# ChladniEagle2.net
KiCad netlist of a schematic drawn in EAGLE
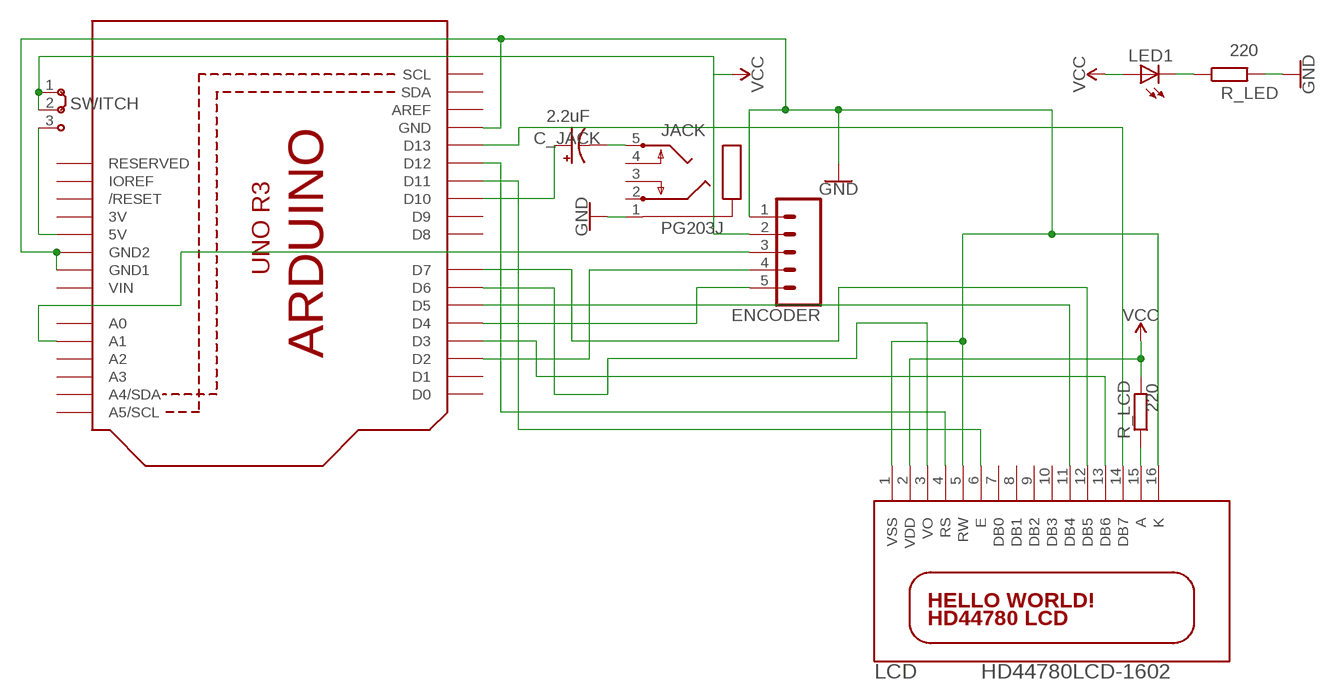
[diagram p0: schematic, sheet 1]

(export (version "E")
  (design (tool "Eeschema 10.0.6"))
  (components
    (comp (ref "C_JACK")
      (value "CPOL-USE2,5-6E")
      (footprint "eagle-import:E2,5-6E")
      (fields (field (name "CAPACITANCIA") "2.2uF"))
      (libsource (lib "eagle-import") (part "CPOL-USE2,5-6E"))
    )
    (comp (ref "ENCODER")
      (value "CONN_05NO_SILK")
      (footprint "eagle-import:1X05_NO_SILK")
      (libsource (lib "eagle-import") (part "CONN_05NO_SILK"))
    )
    (comp (ref "JACK")
      (value "PG203J")
      (footprint "eagle-import:PG203J")
      (libsource (lib "eagle-import") (part "PG203J"))
    )
    (comp (ref "LCD")
      (value "HD44780LCD-1602")
      (footprint "eagle-import:LCD1602")
      (libsource (lib "eagle-import") (part "HD44780LCD-1602"))
    )
    (comp (ref "LED1")
      (value "LED5MM")
      (footprint "eagle-import:LED5MM")
      (libsource (lib "eagle-import") (part "LED5MM"))
    )
    (comp (ref "R_LCD")
      (value "R-EU_0204/7")
      (footprint "eagle-import:0204_7")
      (fields (field (name "RESISTENCIA") "220"))
      (libsource (lib "eagle-import") (part "R-EU_0204/7"))
    )
    (comp (ref "R_LED")
      (value "R-EU_0204/7")
      (footprint "eagle-import:0204_7")
      (fields (field (name "RESISTENCIA") "220"))
      (libsource (lib "eagle-import") (part "R-EU_0204/7"))
    )
    (comp (ref "SWITCH")
      (value "J2X2MM")
      (footprint "eagle-import:04C")
      (libsource (lib "eagle-import") (part "J2X2MM"))
    )
    (comp (ref "U1")
      (value "ARDUINOR3-BPLACE")
      (footprint "eagle-import:ARDUINOR3-BPLACE")
      (libsource (lib "eagle-import") (part "ARDUINOR3-BPLACE"))
    )
  )
  (nets
    (net (code "1") (name "/3V") (class "Default")
      (node (ref "U1") (pin "3V") (pinfunction "3V_3V") (pintype "power_in"))
    )
    (net (code "2") (name "/VIN") (class "Default")
      (node (ref "U1") (pin "VIN") (pinfunction "VIN_VIN") (pintype "power_in"))
    )
    (net (code "3") (name "GND") (class "Default")
      (node (ref "ENCODER") (pin "1") (pinfunction "1_1") (pintype "passive"))
      (node (ref "JACK") (pin "1") (pinfunction "1_1") (pintype "passive"))
      (node (ref "LCD") (pin "1") (pinfunction "VSS_1") (pintype "power_in"))
      (node (ref "LCD") (pin "16") (pinfunction "K_16") (pintype "input"))
      (node (ref "LCD") (pin "5") (pinfunction "RW_5") (pintype "input"))
      (node (ref "R_LED") (pin "2") (pinfunction "2_2") (pintype "passive"))
      (node (ref "U1") (pin "GND") (pinfunction "GND_GND") (pintype "power_in"))
      (node (ref "U1") (pin "GND1") (pinfunction "GND1_GND1") (pintype "power_in"))
      (node (ref "U1") (pin "GND2") (pinfunction "GND2_GND2") (pintype "power_in"))
    )
    (net (code "4") (name "Net-(C_JACK-Pad+)") (class "Default")
      (node (ref "C_JACK") (pin "+") (pinfunction "+_+") (pintype "passive"))
      (node (ref "U1") (pin "D10") (pinfunction "D10_D10") (pintype "bidirectional"))
    )
    (net (code "5") (name "Net-(C_JACK-Pad-)") (class "Default")
      (node (ref "C_JACK") (pin "-") (pinfunction "-_-") (pintype "passive"))
      (node (ref "JACK") (pin "5") (pinfunction "5_5") (pintype "passive"))
    )
    (net (code "6") (name "Net-(ENCODER-Pad3)") (class "Default")
      (node (ref "ENCODER") (pin "3") (pinfunction "3_3") (pintype "passive"))
      (node (ref "U1") (pin "A1") (pinfunction "A1_A1") (pintype "bidirectional"))
    )
    (net (code "7") (name "Net-(ENCODER-Pad4)") (class "Default")
      (node (ref "ENCODER") (pin "4") (pinfunction "4_4") (pintype "passive"))
      (node (ref "U1") (pin "D2") (pinfunction "D2_D2") (pintype "bidirectional"))
    )
    (net (code "8") (name "Net-(ENCODER-Pad5)") (class "Default")
      (node (ref "ENCODER") (pin "5") (pinfunction "5_5") (pintype "passive"))
      (node (ref "U1") (pin "D4") (pinfunction "D4_D4") (pintype "bidirectional"))
    )
    (net (code "9") (name "Net-(LCD-A)") (class "Default")
      (node (ref "LCD") (pin "15") (pinfunction "A_15") (pintype "input"))
      (node (ref "R_LCD") (pin "1") (pinfunction "1_1") (pintype "passive"))
    )
    (net (code "10") (name "Net-(LCD-DB4)") (class "Default")
      (node (ref "LCD") (pin "11") (pinfunction "DB4_11") (pintype "bidirectional"))
      (node (ref "U1") (pin "D5") (pinfunction "D5_D5") (pintype "bidirectional"))
    )
    (net (code "11") (name "Net-(LCD-DB5)") (class "Default")
      (node (ref "LCD") (pin "12") (pinfunction "DB5_12") (pintype "bidirectional"))
      (node (ref "U1") (pin "D7") (pinfunction "D7_D7") (pintype "bidirectional"))
    )
    (net (code "12") (name "Net-(LCD-DB6)") (class "Default")
      (node (ref "LCD") (pin "13") (pinfunction "DB6_13") (pintype "bidirectional"))
      (node (ref "U1") (pin "D3") (pinfunction "D3_D3") (pintype "bidirectional"))
    )
    (net (code "13") (name "Net-(LCD-DB7)") (class "Default")
      (node (ref "LCD") (pin "14") (pinfunction "DB7_14") (pintype "bidirectional"))
      (node (ref "U1") (pin "D13") (pinfunction "D13_D13") (pintype "bidirectional"))
    )
    (net (code "14") (name "Net-(LCD-E)") (class "Default")
      (node (ref "LCD") (pin "6") (pinfunction "E_6") (pintype "input"))
      (node (ref "U1") (pin "D11") (pinfunction "D11_D11") (pintype "bidirectional"))
    )
    (net (code "15") (name "Net-(LCD-RS)") (class "Default")
      (node (ref "LCD") (pin "4") (pinfunction "RS_4") (pintype "input"))
      (node (ref "U1") (pin "D12") (pinfunction "D12_D12") (pintype "bidirectional"))
    )
    (net (code "16") (name "Net-(LCD-VO)") (class "Default")
      (node (ref "LCD") (pin "3") (pinfunction "VO_3") (pintype "input"))
      (node (ref "U1") (pin "D6") (pinfunction "D6_D6") (pintype "bidirectional"))
    )
    (net (code "17") (name "Net-(LED1-C)") (class "Default")
      (node (ref "LED1") (pin "K") (pinfunction "C_K") (pintype "passive"))
      (node (ref "R_LED") (pin "1") (pinfunction "1_1") (pintype "passive"))
    )
    (net (code "18") (name "Net-(SWITCH-Pad3)") (class "Default")
      (node (ref "SWITCH") (pin "3") (pinfunction "3_3") (pintype "passive"))
      (node (ref "U1") (pin "5V") (pinfunction "5V_5V") (pintype "power_in"))
    )
    (net (code "19") (name "VCC") (class "Default")
      (node (ref "ENCODER") (pin "2") (pinfunction "2_2") (pintype "passive"))
      (node (ref "LCD") (pin "2") (pinfunction "VDD_2") (pintype "power_in"))
      (node (ref "LED1") (pin "A") (pinfunction "A_A") (pintype "passive"))
      (node (ref "R_LCD") (pin "2") (pinfunction "2_2") (pintype "passive"))
      (node (ref "SWITCH") (pin "1") (pinfunction "1_1") (pintype "passive"))
      (node (ref "SWITCH") (pin "2") (pinfunction "2_2") (pintype "passive"))
    )
    (net (code "20") (name "unconnected-(JACK-Pad2)") (class "Default")
      (node (ref "JACK") (pin "2") (pinfunction "2_2") (pintype "passive"))
    )
    (net (code "21") (name "unconnected-(JACK-Pad3)") (class "Default")
      (node (ref "JACK") (pin "3") (pinfunction "3_3") (pintype "passive"))
    )
    (net (code "22") (name "unconnected-(JACK-Pad4)") (class "Default")
      (node (ref "JACK") (pin "4") (pinfunction "4_4") (pintype "passive"))
    )
    (net (code "23") (name "unconnected-(LCD-DB0-Pad7)") (class "Default")
      (node (ref "LCD") (pin "7") (pinfunction "DB0_7") (pintype "bidirectional"))
    )
    (net (code "24") (name "unconnected-(LCD-DB1-Pad8)") (class "Default")
      (node (ref "LCD") (pin "8") (pinfunction "DB1_8") (pintype "bidirectional"))
    )
    (net (code "25") (name "unconnected-(LCD-DB2-Pad9)") (class "Default")
      (node (ref "LCD") (pin "9") (pinfunction "DB2_9") (pintype "bidirectional"))
    )
    (net (code "26") (name "unconnected-(LCD-DB3-Pad10)") (class "Default")
      (node (ref "LCD") (pin "10") (pinfunction "DB3_10") (pintype "bidirectional"))
    )
    (net (code "27") (name "unconnected-(U1-A4{slash}SDA-PadA4)") (class "Default")
      (node (ref "U1") (pin "A4") (pinfunction "A4/SDA_A4") (pintype "bidirectional"))
    )
    (net (code "28") (name "unconnected-(U1-A5{slash}SCL-PadA5)") (class "Default")
      (node (ref "U1") (pin "A5") (pinfunction "A5/SCL_A5") (pintype "bidirectional"))
    )
    (net (code "29") (name "unconnected-(U1-PadA0)") (class "Default")
      (node (ref "U1") (pin "A0") (pinfunction "A0_A0") (pintype "bidirectional"))
    )
    (net (code "30") (name "unconnected-(U1-PadA2)") (class "Default")
      (node (ref "U1") (pin "A2") (pinfunction "A2_A2") (pintype "bidirectional"))
    )
    (net (code "31") (name "unconnected-(U1-PadA3)") (class "Default")
      (node (ref "U1") (pin "A3") (pinfunction "A3_A3") (pintype "bidirectional"))
    )
    (net (code "32") (name "unconnected-(U1-PadAREF)") (class "Default")
      (node (ref "U1") (pin "AREF") (pinfunction "AREF_AREF") (pintype "bidirectional"))
    )
    (net (code "33") (name "unconnected-(U1-PadD0)") (class "Default")
      (node (ref "U1") (pin "D0") (pinfunction "D0_D0") (pintype "bidirectional"))
    )
    (net (code "34") (name "unconnected-(U1-PadD1)") (class "Default")
      (node (ref "U1") (pin "D1") (pinfunction "D1_D1") (pintype "bidirectional"))
    )
    (net (code "35") (name "unconnected-(U1-PadD8)") (class "Default")
      (node (ref "U1") (pin "D8") (pinfunction "D8_D8") (pintype "bidirectional"))
    )
    (net (code "36") (name "unconnected-(U1-PadD9)") (class "Default")
      (node (ref "U1") (pin "D9") (pinfunction "D9_D9") (pintype "bidirectional"))
    )
    (net (code "37") (name "unconnected-(U1-PadIOREF)") (class "Default")
      (node (ref "U1") (pin "IOREF") (pinfunction "IOREF_IOREF") (pintype "output"))
    )
    (net (code "38") (name "unconnected-(U1-PadRESERVED)") (class "Default")
      (node (ref "U1") (pin "RESERVED") (pinfunction "RESERVED_RESERVED") (pintype "no_connect"))
    )
    (net (code "39") (name "unconnected-(U1-PadSCL)") (class "Default")
      (node (ref "U1") (pin "SCL") (pinfunction "SCL_SCL") (pintype "bidirectional"))
    )
    (net (code "40") (name "unconnected-(U1-PadSDA)") (class "Default")
      (node (ref "U1") (pin "SDA") (pinfunction "SDA_SDA") (pintype "bidirectional"))
    )
    (net (code "41") (name "unconnected-(U1-{slash}RESET-PadRESET)") (class "Default")
      (node (ref "U1") (pin "RESET") (pinfunction "/RESET_RESET") (pintype "bidirectional"))
    )
  )
)
